# INS_Visualizer.net
KiCad netlist of a schematic drawn in Altium Designer
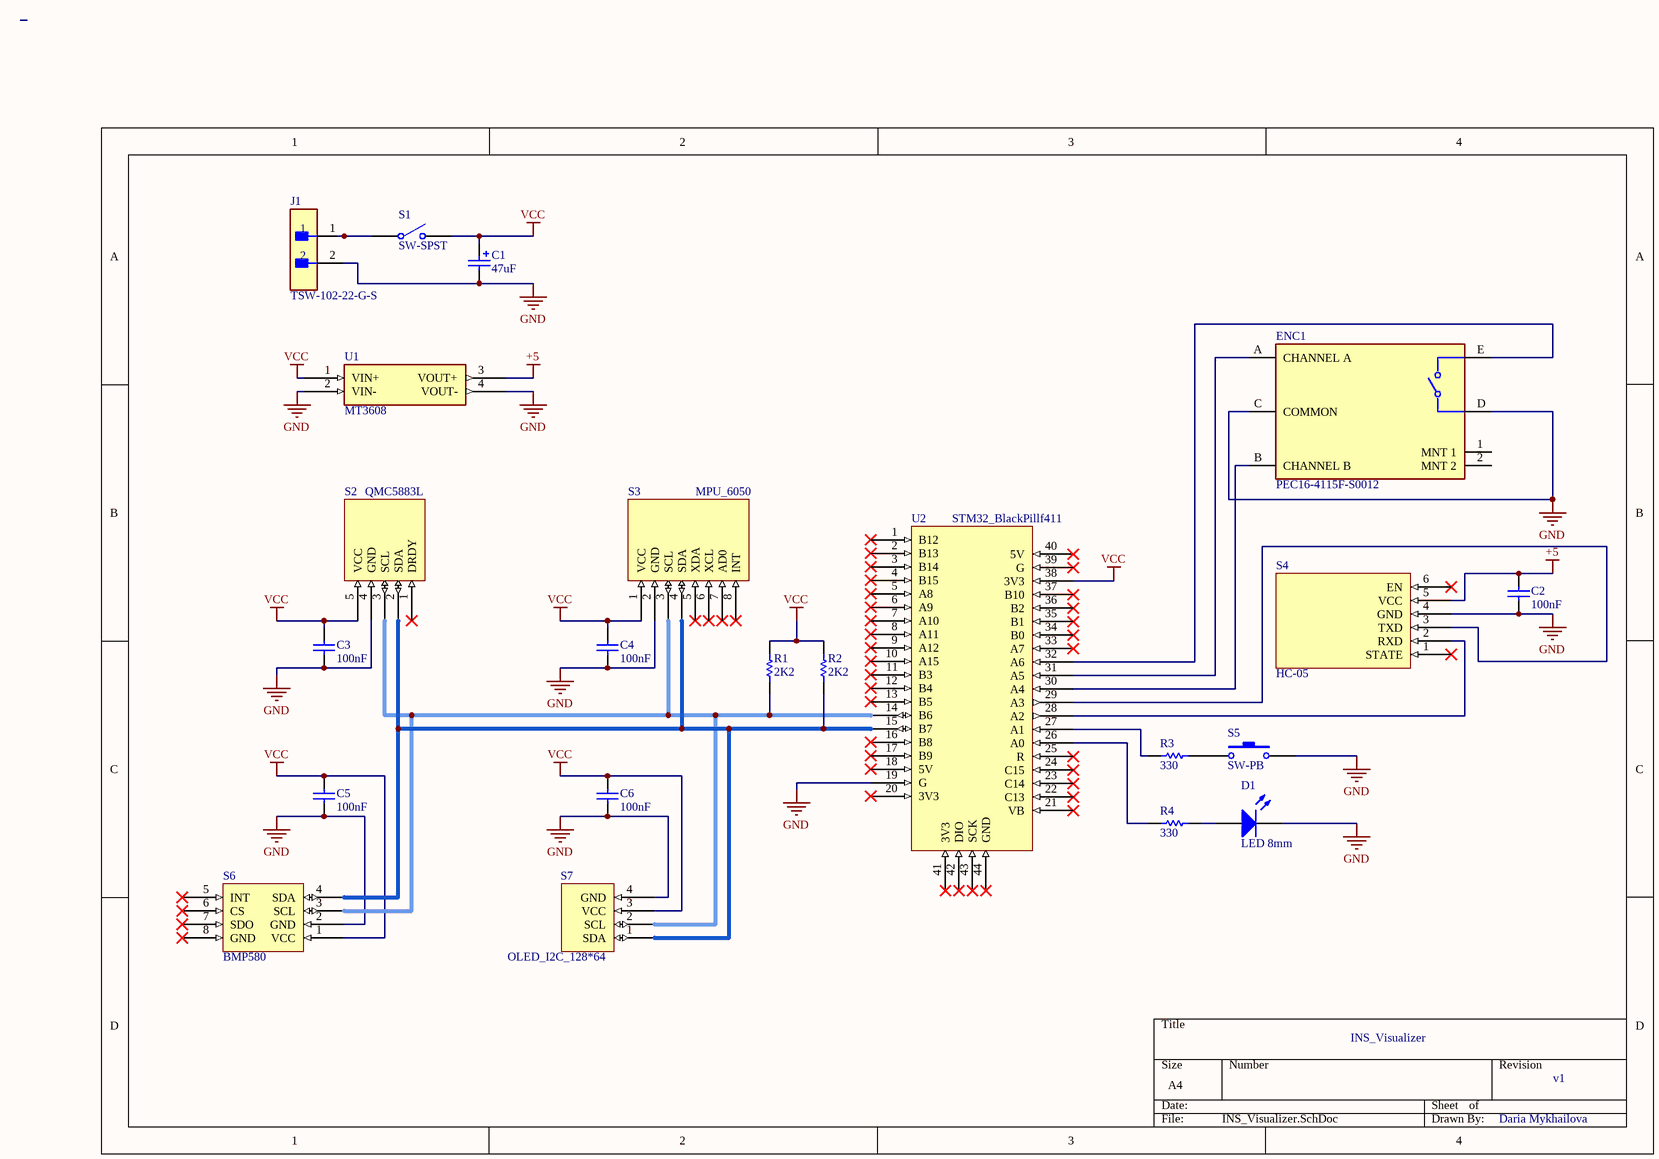
[diagram p0: INS_Visualizer.SchDoc]

(export (version "E")
  (design (tool "Eeschema 10.0.6"))
  (components
    (comp (ref "C1")
      (value "47uF")
      (footprint "Capacitor Pol")
      (description "Polarized Capacitor (Radial)")
      (fields (field (name "Comment") "Capacitor Pol") (field (name "PUBLISHER") "Altium Limited"))
      (libsource (lib "INS") (part "Capacitor Pol"))
    )
    (comp (ref "C2")
      (value "100nF")
      (footprint "RAD-0.3")
      (fields (field (name "Comment") "Capacitor") (field (name "PUBLISHER") "Altium Limited"))
      (libsource (lib "INS") (part "Capacitor"))
    )
    (comp (ref "C3")
      (value "100nF")
      (footprint "RAD-0.3")
      (fields (field (name "Comment") "Capacitor") (field (name "PUBLISHER") "Altium Limited"))
      (libsource (lib "INS") (part "Capacitor"))
    )
    (comp (ref "C4")
      (value "100nF")
      (footprint "RAD-0.3")
      (fields (field (name "Comment") "Capacitor") (field (name "PUBLISHER") "Altium Limited"))
      (libsource (lib "INS") (part "Capacitor"))
    )
    (comp (ref "C5")
      (value "100nF")
      (footprint "RAD-0.3")
      (fields (field (name "Comment") "Capacitor") (field (name "PUBLISHER") "Altium Limited"))
      (libsource (lib "INS") (part "Capacitor"))
    )
    (comp (ref "C6")
      (value "100nF")
      (footprint "RAD-0.3")
      (fields (field (name "Comment") "Capacitor") (field (name "PUBLISHER") "Altium Limited"))
      (libsource (lib "INS") (part "Capacitor"))
    )
    (comp (ref "D1") (value "LED 8mm") (footprint "LED 8mm") (libsource (lib "INS") (part "LED 8mm")))
    (comp (ref "ENC1")
      (value "PEC16-4115F-S0012")
      (footprint "FP-PEC16-4115F-S0012-MFG")
      (description "ROTARY ENCODER MECHANICAL 12PPR")
      (libsource (lib "Altium Content Vault") (part "74e6fcc4b0c7d654d48d7f2a48e5514"))
    )
    (comp (ref "J1")
      (value "TSW-102-22-G-S")
      (footprint "FP-TSW-102-22-G-S-MFG")
      (description "CONN HEADER VERT 2POS 2.54MM")
      (libsource (lib "Altium Content Vault") (part "3bc925449376181038e59eaffc5286c"))
    )
    (comp (ref "R1")
      (value "2K2")
      (footprint "AXIAL-0.3")
      (fields (field (name "Comment") "Resistor") (field (name "PUBLISHER") "Altium Limited"))
      (libsource (lib "INS") (part "Resistor"))
    )
    (comp (ref "R2")
      (value "2K2")
      (footprint "AXIAL-0.3")
      (fields (field (name "Comment") "Resistor") (field (name "PUBLISHER") "Altium Limited"))
      (libsource (lib "INS") (part "Resistor"))
    )
    (comp (ref "R3")
      (value "330")
      (footprint "AXIAL-0.3")
      (fields (field (name "Comment") "Resistor") (field (name "PUBLISHER") "Altium Limited"))
      (libsource (lib "INS") (part "Resistor"))
    )
    (comp (ref "R4")
      (value "330")
      (footprint "AXIAL-0.3")
      (fields (field (name "Comment") "Resistor") (field (name "PUBLISHER") "Altium Limited"))
      (libsource (lib "INS") (part "Resistor"))
    )
    (comp (ref "S1")
      (value "SW-SPST")
      (footprint "SPST-2")
      (description "Single-Pole, Single-Throw Switch")
      (fields (field (name "PUBLISHER") "Altium Limited"))
      (libsource (lib "INS") (part "SW-SPST"))
    )
    (comp (ref "S2") (value "QMC5883L") (footprint "QMC5883L") (libsource (lib "INS") (part "QMC5883L")))
    (comp (ref "S3")
      (value "MPU_6050")
      (footprint "MPU6050_HDR1X8")
      (libsource (lib "INS") (part "MPU_6050"))
    )
    (comp (ref "S4") (value "HC-05") (footprint "HC-05_HDR1x6H") (libsource (lib "INS") (part "HC-05")))
    (comp (ref "S5")
      (value "SW-PB")
      (footprint "SPST-2")
      (description "Switch")
      (fields (field (name "PUBLISHER") "Altium Limited"))
      (libsource (lib "INS") (part "SW-PB"))
    )
    (comp (ref "S6") (value "BMP580") (footprint "BMP580_HDR1x4") (libsource (lib "INS") (part "BMP580")))
    (comp (ref "S7")
      (value "OLED_I2C_128*64")
      (footprint "OLED_HDR1x4")
      (libsource (lib "INS") (part "OLED_I2C_128*64"))
    )
    (comp (ref "U1") (value "MT3608") (footprint "MT3608") (libsource (lib "INS") (part "MT3608")))
    (comp (ref "U2")
      (value "STM32_BlackPillf411")
      (footprint "STM32_HDR2x20")
      (libsource (lib "INS") (part "STM32_BlackPillf411"))
    )
  )
  (nets
    (net (code "1") (name "+5") (class "Default")
      (node (ref "C2") (pin "2") (pinfunction "2_2") (pintype "passive"))
      (node (ref "S4") (pin "5") (pinfunction "VCC_5") (pintype "input"))
      (node (ref "U1") (pin "3") (pinfunction "VOUT+_3") (pintype "output"))
    )
    (net (code "2") (name "GND") (class "Default")
      (node (ref "C1") (pin "2") (pinfunction "2_2") (pintype "passive"))
      (node (ref "C2") (pin "1") (pinfunction "1_1") (pintype "passive"))
      (node (ref "C3") (pin "1") (pinfunction "1_1") (pintype "passive"))
      (node (ref "C4") (pin "1") (pinfunction "1_1") (pintype "passive"))
      (node (ref "C5") (pin "1") (pinfunction "1_1") (pintype "passive"))
      (node (ref "C6") (pin "1") (pinfunction "1_1") (pintype "passive"))
      (node (ref "D1") (pin "2") (pinfunction "2_2") (pintype "passive"))
      (node (ref "ENC1") (pin "C") (pinfunction "COMMON_C") (pintype "passive"))
      (node (ref "ENC1") (pin "D") (pinfunction "D_D") (pintype "passive"))
      (node (ref "J1") (pin "2") (pinfunction "2_2") (pintype "passive"))
      (node (ref "S2") (pin "4") (pinfunction "GND_4") (pintype "input"))
      (node (ref "S3") (pin "2") (pinfunction "GND_2") (pintype "input"))
      (node (ref "S4") (pin "4") (pinfunction "GND_4") (pintype "input"))
      (node (ref "S5") (pin "2") (pinfunction "2_2") (pintype "passive"))
      (node (ref "S6") (pin "2") (pinfunction "GND_2") (pintype "input"))
      (node (ref "S7") (pin "4") (pinfunction "GND_4") (pintype "input"))
      (node (ref "U1") (pin "2") (pinfunction "VIN-_2") (pintype "input"))
      (node (ref "U1") (pin "4") (pinfunction "VOUT-_4") (pintype "output"))
      (node (ref "U2") (pin "19") (pinfunction "G_19") (pintype "input"))
    )
    (net (code "3") (name "Net-(D1-Pad1)") (class "Default")
      (node (ref "D1") (pin "1") (pinfunction "1_1") (pintype "passive"))
      (node (ref "R4") (pin "1") (pinfunction "1_1") (pintype "passive"))
    )
    (net (code "4") (name "Net-(ENC1-CHANNEL_A)") (class "Default")
      (node (ref "ENC1") (pin "A") (pinfunction "CHANNEL_A_A") (pintype "passive"))
      (node (ref "U2") (pin "31") (pinfunction "A5_31") (pintype "input"))
    )
    (net (code "5") (name "Net-(ENC1-CHANNEL_B)") (class "Default")
      (node (ref "ENC1") (pin "B") (pinfunction "CHANNEL_B_B") (pintype "passive"))
      (node (ref "U2") (pin "30") (pinfunction "A4_30") (pintype "input"))
    )
    (net (code "6") (name "Net-(R3-Pad1)") (class "Default")
      (node (ref "R3") (pin "1") (pinfunction "1_1") (pintype "passive"))
      (node (ref "S5") (pin "1") (pinfunction "1_1") (pintype "passive"))
    )
    (net (code "7") (name "Net-(S1-COMMON)") (class "Default")
      (node (ref "J1") (pin "1") (pinfunction "1_1") (pintype "passive"))
      (node (ref "S1") (pin "1") (pinfunction "COMMON_1") (pintype "passive"))
    )
    (net (code "8") (name "Net-(S2-SCL)") (class "Default")
      (node (ref "R1") (pin "1") (pinfunction "1_1") (pintype "passive"))
      (node (ref "S2") (pin "3") (pinfunction "SCL_3") (pintype "bidirectional"))
      (node (ref "S3") (pin "3") (pinfunction "SCL_3") (pintype "bidirectional"))
      (node (ref "S6") (pin "3") (pinfunction "SCL_3") (pintype "bidirectional"))
      (node (ref "S7") (pin "2") (pinfunction "SCL_2") (pintype "bidirectional"))
      (node (ref "U2") (pin "14") (pinfunction "B6_14") (pintype "bidirectional"))
    )
    (net (code "9") (name "Net-(S2-SDA)") (class "Default")
      (node (ref "R2") (pin "1") (pinfunction "1_1") (pintype "passive"))
      (node (ref "S2") (pin "2") (pinfunction "SDA_2") (pintype "bidirectional"))
      (node (ref "S3") (pin "4") (pinfunction "SDA_4") (pintype "bidirectional"))
      (node (ref "S6") (pin "4") (pinfunction "SDA_4") (pintype "bidirectional"))
      (node (ref "S7") (pin "1") (pinfunction "SDA_1") (pintype "bidirectional"))
      (node (ref "U2") (pin "15") (pinfunction "B7_15") (pintype "bidirectional"))
    )
    (net (code "10") (name "Net-(S4-RXD)") (class "Default")
      (node (ref "S4") (pin "2") (pinfunction "RXD_2") (pintype "input"))
      (node (ref "U2") (pin "28") (pinfunction "A2_28") (pintype "output"))
    )
    (net (code "11") (name "Net-(S4-TXD)") (class "Default")
      (node (ref "S4") (pin "3") (pinfunction "TXD_3") (pintype "input"))
      (node (ref "U2") (pin "29") (pinfunction "A3_29") (pintype "output"))
    )
    (net (code "12") (name "Net-(U2-A0)") (class "Default")
      (node (ref "R4") (pin "2") (pinfunction "2_2") (pintype "passive"))
      (node (ref "U2") (pin "26") (pinfunction "A0_26") (pintype "input"))
    )
    (net (code "13") (name "Net-(U2-A1)") (class "Default")
      (node (ref "R3") (pin "2") (pinfunction "2_2") (pintype "passive"))
      (node (ref "U2") (pin "27") (pinfunction "A1_27") (pintype "input"))
    )
    (net (code "14") (name "Net-(U2-A6)") (class "Default")
      (node (ref "ENC1") (pin "E") (pinfunction "E_E") (pintype "passive"))
      (node (ref "U2") (pin "32") (pinfunction "A6_32") (pintype "input"))
    )
    (net (code "15") (name "VCC") (class "Default")
      (node (ref "C1") (pin "1") (pinfunction "1_1") (pintype "passive"))
      (node (ref "C3") (pin "2") (pinfunction "2_2") (pintype "passive"))
      (node (ref "C4") (pin "2") (pinfunction "2_2") (pintype "passive"))
      (node (ref "C5") (pin "2") (pinfunction "2_2") (pintype "passive"))
      (node (ref "C6") (pin "2") (pinfunction "2_2") (pintype "passive"))
      (node (ref "R1") (pin "2") (pinfunction "2_2") (pintype "passive"))
      (node (ref "R2") (pin "2") (pinfunction "2_2") (pintype "passive"))
      (node (ref "S1") (pin "2") (pinfunction "NO_2") (pintype "passive"))
      (node (ref "S2") (pin "5") (pinfunction "VCC_5") (pintype "input"))
      (node (ref "S3") (pin "1") (pinfunction "VCC_1") (pintype "input"))
      (node (ref "S6") (pin "1") (pinfunction "VCC_1") (pintype "input"))
      (node (ref "S7") (pin "3") (pinfunction "VCC_3") (pintype "input"))
      (node (ref "U1") (pin "1") (pinfunction "VIN+_1") (pintype "input"))
      (node (ref "U2") (pin "38") (pinfunction "3V3_38") (pintype "input"))
    )
    (net (code "16") (name "unconnected-(ENC1-MNT_1-Pad1)") (class "Default")
      (node (ref "ENC1") (pin "1") (pinfunction "MNT_1_1") (pintype "passive"))
    )
    (net (code "17") (name "unconnected-(ENC1-MNT_2-Pad2)") (class "Default")
      (node (ref "ENC1") (pin "2") (pinfunction "MNT_2_2") (pintype "passive"))
    )
    (net (code "18") (name "unconnected-(S2-DRDY-Pad1)") (class "Default")
      (node (ref "S2") (pin "1") (pinfunction "DRDY_1") (pintype "input+no_connect"))
    )
    (net (code "19") (name "unconnected-(S3-AD0-Pad7)") (class "Default")
      (node (ref "S3") (pin "7") (pinfunction "AD0_7") (pintype "input+no_connect"))
    )
    (net (code "20") (name "unconnected-(S3-INT-Pad8)") (class "Default")
      (node (ref "S3") (pin "8") (pinfunction "INT_8") (pintype "input+no_connect"))
    )
    (net (code "21") (name "unconnected-(S3-XCL-Pad6)") (class "Default")
      (node (ref "S3") (pin "6") (pinfunction "XCL_6") (pintype "input+no_connect"))
    )
    (net (code "22") (name "unconnected-(S3-XDA-Pad5)") (class "Default")
      (node (ref "S3") (pin "5") (pinfunction "XDA_5") (pintype "input+no_connect"))
    )
    (net (code "23") (name "unconnected-(S4-EN-Pad6)") (class "Default")
      (node (ref "S4") (pin "6") (pinfunction "EN_6") (pintype "input+no_connect"))
    )
    (net (code "24") (name "unconnected-(S4-STATE-Pad1)") (class "Default")
      (node (ref "S4") (pin "1") (pinfunction "STATE_1") (pintype "input+no_connect"))
    )
    (net (code "25") (name "unconnected-(S6-CS-Pad6)") (class "Default")
      (node (ref "S6") (pin "6") (pinfunction "CS_6") (pintype "input+no_connect"))
    )
    (net (code "26") (name "unconnected-(S6-GND-Pad8)") (class "Default")
      (node (ref "S6") (pin "8") (pinfunction "GND_8") (pintype "input+no_connect"))
    )
    (net (code "27") (name "unconnected-(S6-INT-Pad5)") (class "Default")
      (node (ref "S6") (pin "5") (pinfunction "INT_5") (pintype "input+no_connect"))
    )
    (net (code "28") (name "unconnected-(S6-SDO-Pad7)") (class "Default")
      (node (ref "S6") (pin "7") (pinfunction "SDO_7") (pintype "input+no_connect"))
    )
    (net (code "29") (name "unconnected-(U2-3V3-Pad20)") (class "Default")
      (node (ref "U2") (pin "20") (pinfunction "3V3_20") (pintype "input+no_connect"))
    )
    (net (code "30") (name "unconnected-(U2-3V3-Pad41)") (class "Default")
      (node (ref "U2") (pin "41") (pinfunction "3V3_41") (pintype "input+no_connect"))
    )
    (net (code "31") (name "unconnected-(U2-5V-Pad18)") (class "Default")
      (node (ref "U2") (pin "18") (pinfunction "5V_18") (pintype "input+no_connect"))
    )
    (net (code "32") (name "unconnected-(U2-5V-Pad40)") (class "Default")
      (node (ref "U2") (pin "40") (pinfunction "5V_40") (pintype "input+no_connect"))
    )
    (net (code "33") (name "unconnected-(U2-A7-Pad33)") (class "Default")
      (node (ref "U2") (pin "33") (pinfunction "A7_33") (pintype "input+no_connect"))
    )
    (net (code "34") (name "unconnected-(U2-A8-Pad5)") (class "Default")
      (node (ref "U2") (pin "5") (pinfunction "A8_5") (pintype "input+no_connect"))
    )
    (net (code "35") (name "unconnected-(U2-A9-Pad6)") (class "Default")
      (node (ref "U2") (pin "6") (pinfunction "A9_6") (pintype "input+no_connect"))
    )
    (net (code "36") (name "unconnected-(U2-A10-Pad7)") (class "Default")
      (node (ref "U2") (pin "7") (pinfunction "A10_7") (pintype "input+no_connect"))
    )
    (net (code "37") (name "unconnected-(U2-A11-Pad8)") (class "Default")
      (node (ref "U2") (pin "8") (pinfunction "A11_8") (pintype "input+no_connect"))
    )
    (net (code "38") (name "unconnected-(U2-A12-Pad9)") (class "Default")
      (node (ref "U2") (pin "9") (pinfunction "A12_9") (pintype "input+no_connect"))
    )
    (net (code "39") (name "unconnected-(U2-A15-Pad10)") (class "Default")
      (node (ref "U2") (pin "10") (pinfunction "A15_10") (pintype "input+no_connect"))
    )
    (net (code "40") (name "unconnected-(U2-B0-Pad34)") (class "Default")
      (node (ref "U2") (pin "34") (pinfunction "B0_34") (pintype "input+no_connect"))
    )
    (net (code "41") (name "unconnected-(U2-B1-Pad35)") (class "Default")
      (node (ref "U2") (pin "35") (pinfunction "B1_35") (pintype "input+no_connect"))
    )
    (net (code "42") (name "unconnected-(U2-B2-Pad36)") (class "Default")
      (node (ref "U2") (pin "36") (pinfunction "B2_36") (pintype "input+no_connect"))
    )
    (net (code "43") (name "unconnected-(U2-B3-Pad11)") (class "Default")
      (node (ref "U2") (pin "11") (pinfunction "B3_11") (pintype "input+no_connect"))
    )
    (net (code "44") (name "unconnected-(U2-B4-Pad12)") (class "Default")
      (node (ref "U2") (pin "12") (pinfunction "B4_12") (pintype "input+no_connect"))
    )
    (net (code "45") (name "unconnected-(U2-B5-Pad13)") (class "Default")
      (node (ref "U2") (pin "13") (pinfunction "B5_13") (pintype "input+no_connect"))
    )
    (net (code "46") (name "unconnected-(U2-B8-Pad16)") (class "Default")
      (node (ref "U2") (pin "16") (pinfunction "B8_16") (pintype "input+no_connect"))
    )
    (net (code "47") (name "unconnected-(U2-B9-Pad17)") (class "Default")
      (node (ref "U2") (pin "17") (pinfunction "B9_17") (pintype "input+no_connect"))
    )
    (net (code "48") (name "unconnected-(U2-B10-Pad37)") (class "Default")
      (node (ref "U2") (pin "37") (pinfunction "B10_37") (pintype "input+no_connect"))
    )
    (net (code "49") (name "unconnected-(U2-B12-Pad1)") (class "Default")
      (node (ref "U2") (pin "1") (pinfunction "B12_1") (pintype "input+no_connect"))
    )
    (net (code "50") (name "unconnected-(U2-B13-Pad2)") (class "Default")
      (node (ref "U2") (pin "2") (pinfunction "B13_2") (pintype "input+no_connect"))
    )
    (net (code "51") (name "unconnected-(U2-B14-Pad3)") (class "Default")
      (node (ref "U2") (pin "3") (pinfunction "B14_3") (pintype "input+no_connect"))
    )
    (net (code "52") (name "unconnected-(U2-B15-Pad4)") (class "Default")
      (node (ref "U2") (pin "4") (pinfunction "B15_4") (pintype "input+no_connect"))
    )
    (net (code "53") (name "unconnected-(U2-C13-Pad22)") (class "Default")
      (node (ref "U2") (pin "22") (pinfunction "C13_22") (pintype "input+no_connect"))
    )
    (net (code "54") (name "unconnected-(U2-C14-Pad23)") (class "Default")
      (node (ref "U2") (pin "23") (pinfunction "C14_23") (pintype "input+no_connect"))
    )
    (net (code "55") (name "unconnected-(U2-C15-Pad24)") (class "Default")
      (node (ref "U2") (pin "24") (pinfunction "C15_24") (pintype "input+no_connect"))
    )
    (net (code "56") (name "unconnected-(U2-DIO-Pad42)") (class "Default")
      (node (ref "U2") (pin "42") (pinfunction "DIO_42") (pintype "input+no_connect"))
    )
    (net (code "57") (name "unconnected-(U2-G-Pad39)") (class "Default")
      (node (ref "U2") (pin "39") (pinfunction "G_39") (pintype "input+no_connect"))
    )
    (net (code "58") (name "unconnected-(U2-GND-Pad44)") (class "Default")
      (node (ref "U2") (pin "44") (pinfunction "GND_44") (pintype "input+no_connect"))
    )
    (net (code "59") (name "unconnected-(U2-R-Pad25)") (class "Default")
      (node (ref "U2") (pin "25") (pinfunction "R_25") (pintype "input+no_connect"))
    )
    (net (code "60") (name "unconnected-(U2-SCK-Pad43)") (class "Default")
      (node (ref "U2") (pin "43") (pinfunction "SCK_43") (pintype "input+no_connect"))
    )
    (net (code "61") (name "unconnected-(U2-VB-Pad21)") (class "Default")
      (node (ref "U2") (pin "21") (pinfunction "VB_21") (pintype "input+no_connect"))
    )
  )
)
